# 1WB_DS2502_ID.net
KiCad netlist of a schematic drawn in Altium Designer
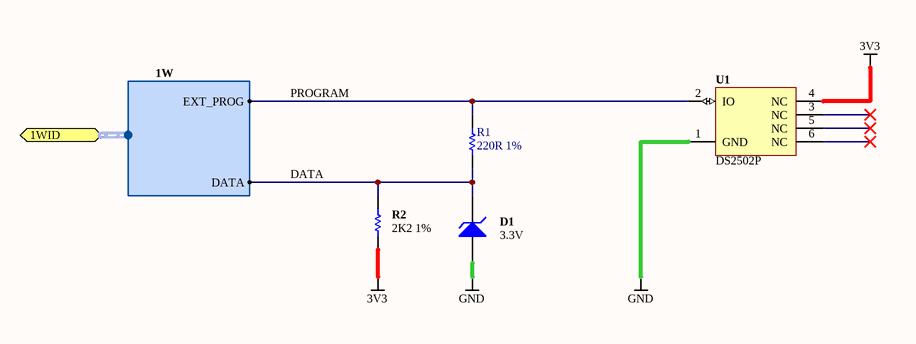
[diagram p0: 1WB_DS2502_ID.SchDoc]

(export (version "E")
  (design (tool "Eeschema 10.0.6"))
  (components
    (comp (ref "D1")
      (value "3.3V")
      (footprint "SOT95P230-3D")
      (description "Zener Diode, 3.3V")
      (libsource (lib "altium-import") (part "root_1_DIO-ZENER-1-3_"))
    )
    (comp (ref "R1")
      (value "220R 1%")
      (footprint "RESC1005-STAR")
      (description "Resistor, 220R 1% 0402 (1005)")
      (fields (field (name "TOLERANCE") "1 %"))
      (libsource (lib "AltiumDesignLibrary") (part "RES"))
    )
    (comp (ref "R2")
      (value "2K2 1%")
      (footprint "RESC1005-STAR")
      (description "Resistor, 2K2 1% 0402 (1005)")
      (fields (field (name "TOLERANCE") "1 %"))
      (libsource (lib "AltiumDesignLibrary") (part "RES"))
    )
    (comp (ref "U1")
      (value "DS2502P")
      (footprint "DSO-C6-D4")
      (description "EPROM, 1-wire, 1024-bit, Surface Mount")
      (libsource (lib "AltiumDesignLibrary") (part "DS2431P"))
    )
  )
  (nets
    (net (code "2") (name "/DATA") (class "Default")
      (node (ref "D1") (pin "2") (pinfunction "K_2") (pintype "passive"))
      (node (ref "R1") (pin "2") (pinfunction "2_2") (pintype "passive"))
      (node (ref "R2") (pin "1") (pinfunction "1_1") (pintype "passive"))
    )
    (net (code "3") (name "/PROGRAM") (class "Default")
      (node (ref "R1") (pin "1") (pinfunction "1_1") (pintype "passive"))
      (node (ref "U1") (pin "2") (pinfunction "IO_2") (pintype "bidirectional"))
    )
    (net (code "5") (name "3V3") (class "Default")
      (node (ref "R2") (pin "2") (pinfunction "2_2") (pintype "passive"))
      (node (ref "U1") (pin "4") (pinfunction "NC_4") (pintype "passive"))
    )
    (net (code "6") (name "GND") (class "Default")
      (node (ref "D1") (pin "1") (pinfunction "A_1") (pintype "passive"))
      (node (ref "U1") (pin "1") (pinfunction "GND_1") (pintype "power_in"))
    )
    (net (code "7") (name "unconnected-(U1-NC-Pad3)") (class "Default")
      (node (ref "U1") (pin "3") (pinfunction "NC_3") (pintype "passive+no_connect"))
    )
    (net (code "8") (name "unconnected-(U1-NC-Pad5)") (class "Default")
      (node (ref "U1") (pin "5") (pinfunction "NC_5") (pintype "passive+no_connect"))
    )
    (net (code "9") (name "unconnected-(U1-NC-Pad6)") (class "Default")
      (node (ref "U1") (pin "6") (pinfunction "NC_6") (pintype "passive+no_connect"))
    )
  )
)
